# BlinkyTile_Controller.net
KiCad netlist of a schematic drawn in EAGLE
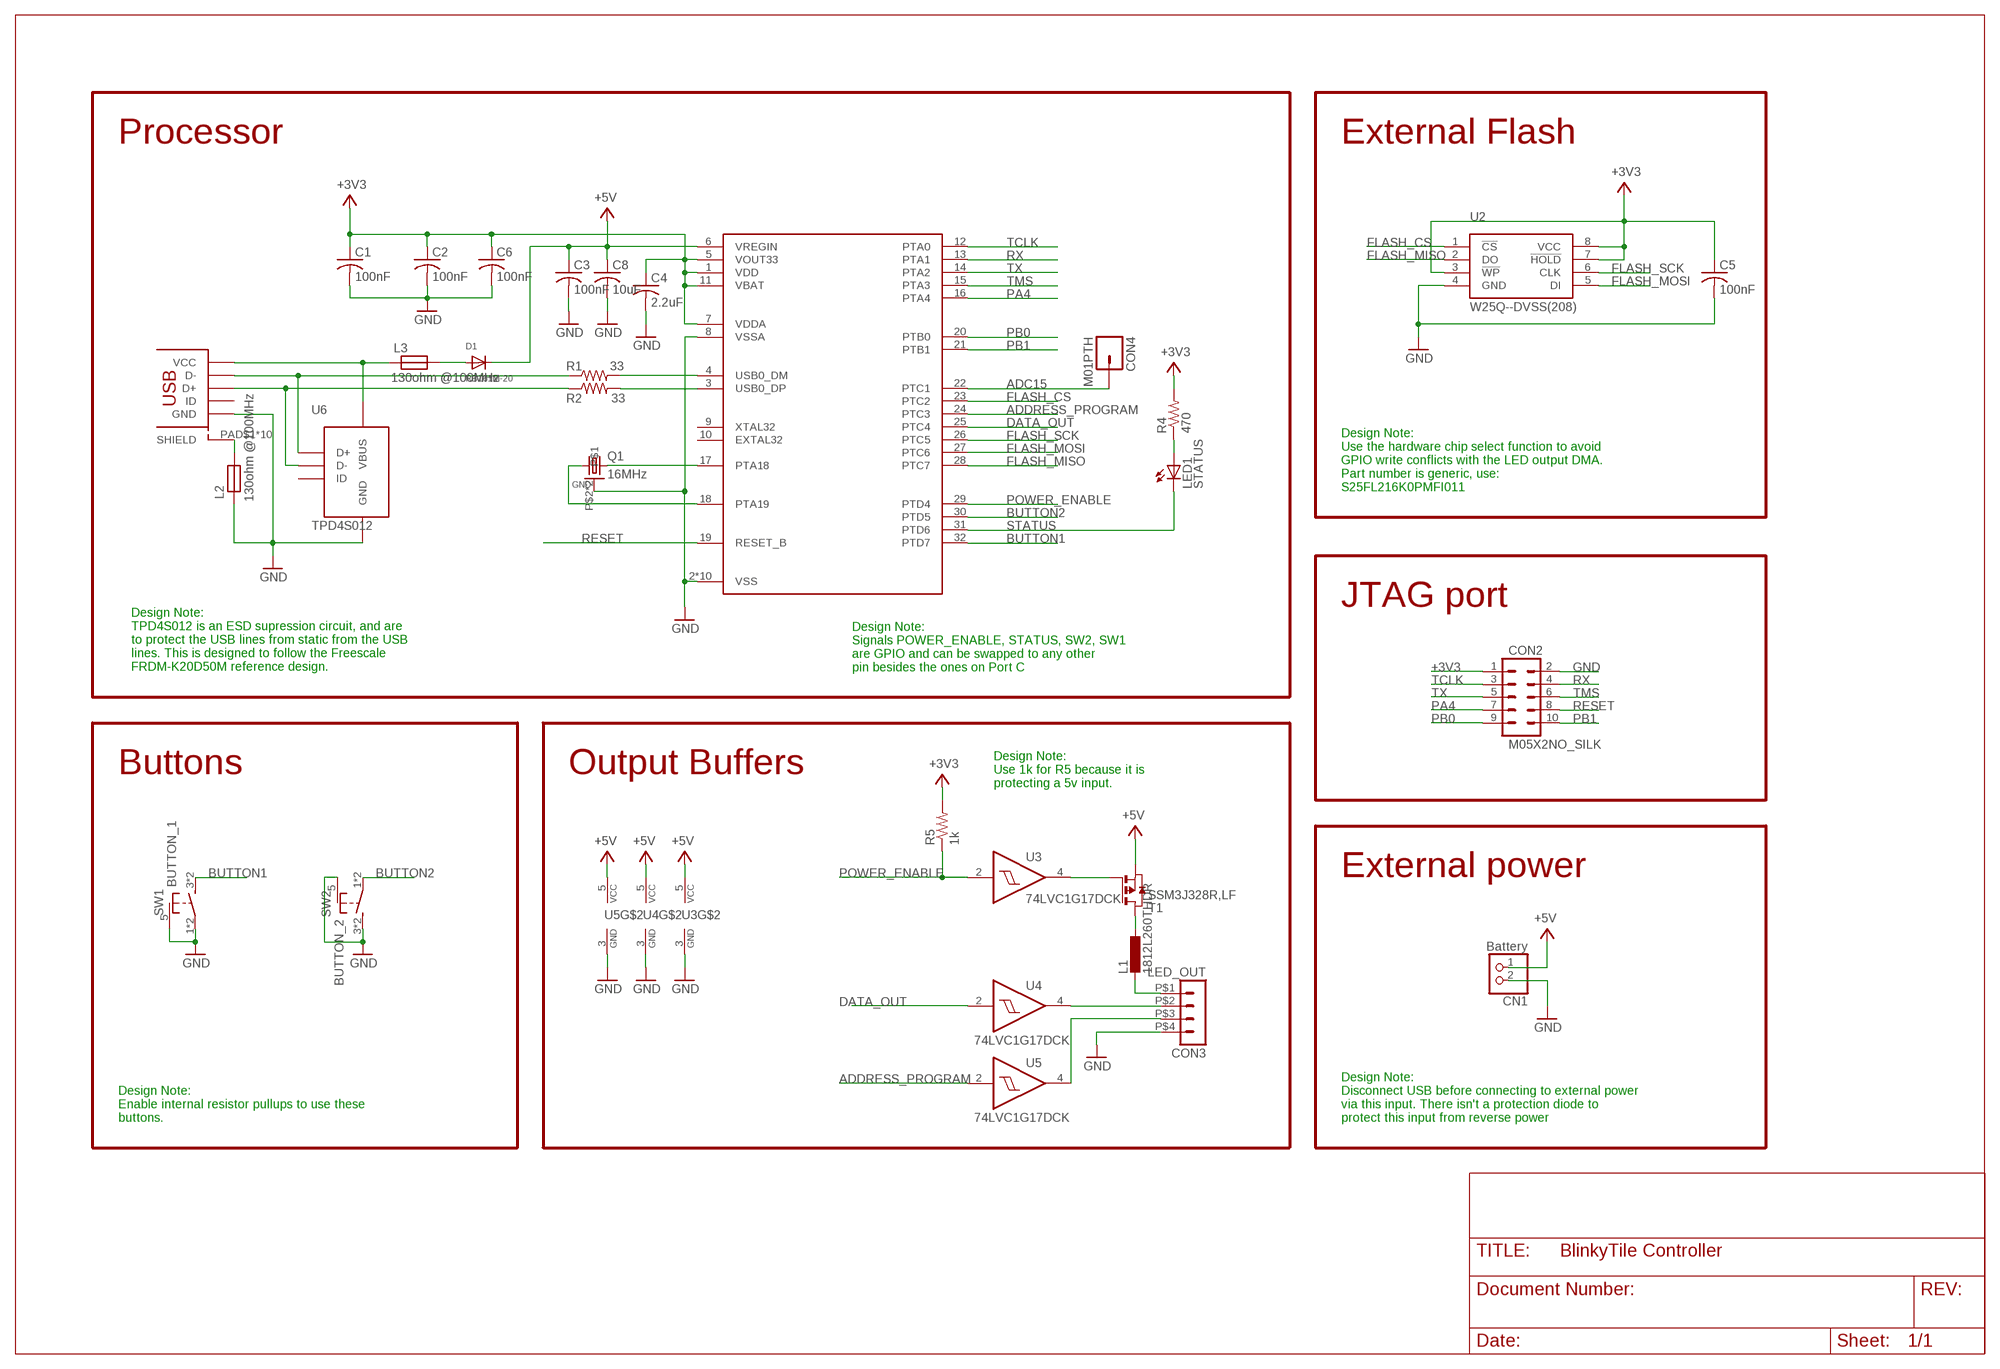
[diagram p0: schematic, sheet 1]

(export (version "E")
  (design (tool "Eeschema 10.0.6"))
  (components
    (comp (ref "C1")
      (value "100nF")
      (footprint "eagle-import:C0402")
      (libsource (lib "eagle-import") (part "C-USC0402"))
    )
    (comp (ref "C2")
      (value "100nF")
      (footprint "eagle-import:C0402")
      (libsource (lib "eagle-import") (part "C-USC0402"))
    )
    (comp (ref "C3")
      (value "100nF")
      (footprint "eagle-import:C0402")
      (libsource (lib "eagle-import") (part "C-USC0402"))
    )
    (comp (ref "C4")
      (value "2.2uF")
      (footprint "eagle-import:C0402")
      (libsource (lib "eagle-import") (part "C-USC0402"))
    )
    (comp (ref "C5")
      (value "100nF")
      (footprint "eagle-import:C0402")
      (libsource (lib "eagle-import") (part "C-USC0402"))
    )
    (comp (ref "C6")
      (value "100nF")
      (footprint "eagle-import:C0402")
      (libsource (lib "eagle-import") (part "C-USC0402"))
    )
    (comp (ref "C8")
      (value "10uF")
      (footprint "eagle-import:C0805K")
      (libsource (lib "eagle-import") (part "C-USC0805K"))
    )
    (comp (ref "CN1")
      (value "Battery")
      (footprint "eagle-import:JST-PH-2-THM-RA")
      (libsource (lib "eagle-import") (part "JST_2PIN-THM-RA"))
    )
    (comp (ref "CON1")
      (value "USB_MICROSMT+THRUHULE")
      (footprint "eagle-import:USB_MICRO_THRUHOLE")
      (libsource (lib "eagle-import") (part "USB_MICROSMT+THRUHULE"))
    )
    (comp (ref "CON2")
      (value "M05X2NO_SILK")
      (footprint "eagle-import:2X5_NOSILK")
      (libsource (lib "eagle-import") (part "M05X2NO_SILK"))
    )
    (comp (ref "CON3")
      (value "LED_OUT")
      (footprint "eagle-import:DUPONT-4P")
      (libsource (lib "eagle-import") (part "4-PIN_DUPONT"))
    )
    (comp (ref "CON4")
      (value "M01PTH")
      (footprint "eagle-import:1X01")
      (libsource (lib "eagle-import") (part "M01PTH"))
    )
    (comp (ref "D1")
      (value "RB161M-20")
      (footprint "eagle-import:SOD-123")
      (libsource (lib "eagle-import") (part "DIODESOD-123"))
    )
    (comp (ref "L1")
      (value "1812L260THDR")
      (footprint "eagle-import:L1812")
      (libsource (lib "eagle-import") (part "L-EUL1812"))
    )
    (comp (ref "L2")
      (value "130ohm @100MHz")
      (footprint "eagle-import:0805")
      (libsource (lib "eagle-import") (part "FB0805/NO-OUTLINE"))
    )
    (comp (ref "L3")
      (value "130ohm @100MHz")
      (footprint "eagle-import:0805")
      (libsource (lib "eagle-import") (part "FB0805/NO-OUTLINE"))
    )
    (comp (ref "LED1")
      (value "STATUS")
      (footprint "eagle-import:CHIPLED_0805")
      (libsource (lib "eagle-import") (part "LEDCHIPLED_0805"))
    )
    (comp (ref "Q1")
      (value "16MHz")
      (footprint "eagle-import:CRSYTAL_2520")
      (libsource (lib "eagle-import") (part "CRYSTAL_4PAD2520"))
    )
    (comp (ref "R1")
      (value "33")
      (footprint "eagle-import:R0402")
      (libsource (lib "eagle-import") (part "R-US_R0402"))
    )
    (comp (ref "R2")
      (value "33")
      (footprint "eagle-import:R0402")
      (libsource (lib "eagle-import") (part "R-US_R0402"))
    )
    (comp (ref "R4")
      (value "470")
      (footprint "eagle-import:R0402")
      (libsource (lib "eagle-import") (part "R-US_R0402"))
    )
    (comp (ref "R5")
      (value "1k")
      (footprint "eagle-import:R0402")
      (libsource (lib "eagle-import") (part "R-US_R0402"))
    )
    (comp (ref "SW1")
      (value "BUTTON_1")
      (footprint "eagle-import:TD-07XB")
      (libsource (lib "eagle-import") (part "BUTTON_MOMENTARY_GROUND"))
    )
    (comp (ref "SW2")
      (value "BUTTON_2")
      (footprint "eagle-import:TD-07XB")
      (libsource (lib "eagle-import") (part "BUTTON_MOMENTARY_GROUND"))
    )
    (comp (ref "T1")
      (value "SSM3J328R,LF")
      (footprint "eagle-import:SOT-23")
      (libsource (lib "eagle-import") (part "PMOSSOT23"))
    )
    (comp (ref "U1")
      (value "MK20D--VFM5")
      (footprint "eagle-import:QFN32_5X5_LONGLEADS")
      (libsource (lib "eagle-import") (part "MK20D--VFM5"))
    )
    (comp (ref "U2")
      (value "W25Q--DVSS(208)")
      (footprint "eagle-import:SOIC8-208")
      (libsource (lib "eagle-import") (part "W25Q--DVSS(208)"))
    )
    (comp (ref "U3")
      (value "74LVC1G17DCK")
      (footprint "eagle-import:SC70-5")
      (libsource (lib "eagle-import") (part "741G17DCKLVC"))
    )
    (comp (ref "U4")
      (value "74LVC1G17DCK")
      (footprint "eagle-import:SC70-5")
      (libsource (lib "eagle-import") (part "741G17DCKLVC"))
    )
    (comp (ref "U5")
      (value "74LVC1G17DCK")
      (footprint "eagle-import:SC70-5")
      (libsource (lib "eagle-import") (part "741G17DCKLVC"))
    )
    (comp (ref "U6")
      (value "TPD4S012")
      (footprint "eagle-import:R-PUSON-N6")
      (libsource (lib "eagle-import") (part "TPD4S012"))
    )
  )
  (nets
    (net (code "1") (name "+3V3") (class "Default")
      (node (ref "C1") (pin "1") (pinfunction "1_1") (pintype "passive"))
      (node (ref "C2") (pin "1") (pinfunction "1_1") (pintype "passive"))
      (node (ref "C4") (pin "1") (pinfunction "1_1") (pintype "passive"))
      (node (ref "C5") (pin "1") (pinfunction "1_1") (pintype "passive"))
      (node (ref "C6") (pin "1") (pinfunction "1_1") (pintype "passive"))
      (node (ref "CON2") (pin "1") (pinfunction "1_1") (pintype "passive"))
      (node (ref "R4") (pin "2") (pinfunction "2_2") (pintype "passive"))
      (node (ref "R5") (pin "2") (pinfunction "2_2") (pintype "passive"))
      (node (ref "U1") (pin "1") (pinfunction "VDD_1") (pintype "bidirectional"))
      (node (ref "U1") (pin "11") (pinfunction "VBAT_11") (pintype "bidirectional"))
      (node (ref "U1") (pin "5") (pinfunction "VOUT33_5") (pintype "bidirectional"))
      (node (ref "U1") (pin "7") (pinfunction "VDDA_7") (pintype "bidirectional"))
      (node (ref "U2") (pin "3") (pinfunction "~{WP}_3") (pintype "bidirectional"))
      (node (ref "U2") (pin "7") (pinfunction "~{HOLD}_7") (pintype "bidirectional"))
      (node (ref "U2") (pin "8") (pinfunction "VCC_8") (pintype "bidirectional"))
    )
    (net (code "2") (name "+5V") (class "Default")
      (node (ref "C3") (pin "1") (pinfunction "1_1") (pintype "passive"))
      (node (ref "C8") (pin "1") (pinfunction "1_1") (pintype "passive"))
      (node (ref "CN1") (pin "1") (pinfunction "2_1") (pintype "passive"))
      (node (ref "D1") (pin "C") (pinfunction "C_C") (pintype "passive"))
      (node (ref "T1") (pin "2") (pinfunction "S_2") (pintype "passive"))
      (node (ref "U1") (pin "6") (pinfunction "VREGIN_6") (pintype "bidirectional"))
      (node (ref "U3") (pin "5") (pinfunction "VCC_5") (pintype "power_in"))
      (node (ref "U4") (pin "5") (pinfunction "VCC_5") (pintype "power_in"))
      (node (ref "U5") (pin "5") (pinfunction "VCC_5") (pintype "power_in"))
    )
    (net (code "3") (name "/ADC15") (class "Default")
      (node (ref "CON4") (pin "1") (pinfunction "1_1") (pintype "passive"))
      (node (ref "U1") (pin "22") (pinfunction "PTC1_22") (pintype "bidirectional"))
    )
    (net (code "4") (name "/ADDRESS_PROGRAM") (class "Default")
      (node (ref "U1") (pin "24") (pinfunction "PTC3_24") (pintype "bidirectional"))
      (node (ref "U5") (pin "2") (pinfunction "I_2") (pintype "input"))
    )
    (net (code "5") (name "/BUTTON1") (class "Default")
      (node (ref "SW1") (pin "3") (pinfunction "S_3") (pintype "passive"))
      (node (ref "SW1") (pin "4") (pinfunction "S_4") (pintype "passive"))
      (node (ref "U1") (pin "32") (pinfunction "PTD7_32") (pintype "bidirectional"))
    )
    (net (code "6") (name "/BUTTON2") (class "Default")
      (node (ref "SW2") (pin "1") (pinfunction "P_1") (pintype "passive"))
      (node (ref "SW2") (pin "2") (pinfunction "P_2") (pintype "passive"))
      (node (ref "U1") (pin "30") (pinfunction "PTD5_30") (pintype "bidirectional"))
    )
    (net (code "7") (name "/DATA_OUT") (class "Default")
      (node (ref "U1") (pin "25") (pinfunction "PTC4_25") (pintype "bidirectional"))
      (node (ref "U4") (pin "2") (pinfunction "I_2") (pintype "input"))
    )
    (net (code "8") (name "/FLASH_CS") (class "Default")
      (node (ref "U1") (pin "23") (pinfunction "PTC2_23") (pintype "bidirectional"))
      (node (ref "U2") (pin "1") (pinfunction "~{CS}_1") (pintype "bidirectional"))
    )
    (net (code "9") (name "/FLASH_MISO") (class "Default")
      (node (ref "U1") (pin "28") (pinfunction "PTC7_28") (pintype "bidirectional"))
      (node (ref "U2") (pin "2") (pinfunction "DO_2") (pintype "bidirectional"))
    )
    (net (code "10") (name "/FLASH_MOSI") (class "Default")
      (node (ref "U1") (pin "27") (pinfunction "PTC6_27") (pintype "bidirectional"))
      (node (ref "U2") (pin "5") (pinfunction "DI_5") (pintype "bidirectional"))
    )
    (net (code "11") (name "/FLASH_SCK") (class "Default")
      (node (ref "U1") (pin "26") (pinfunction "PTC5_26") (pintype "bidirectional"))
      (node (ref "U2") (pin "6") (pinfunction "CLK_6") (pintype "bidirectional"))
    )
    (net (code "12") (name "/PA4") (class "Default")
      (node (ref "CON2") (pin "7") (pinfunction "7_7") (pintype "passive"))
      (node (ref "U1") (pin "16") (pinfunction "PTA4_16") (pintype "bidirectional"))
    )
    (net (code "13") (name "/PB0") (class "Default")
      (node (ref "CON2") (pin "9") (pinfunction "9_9") (pintype "passive"))
      (node (ref "U1") (pin "20") (pinfunction "PTB0_20") (pintype "bidirectional"))
    )
    (net (code "14") (name "/PB1") (class "Default")
      (node (ref "CON2") (pin "10") (pinfunction "10_10") (pintype "passive"))
      (node (ref "U1") (pin "21") (pinfunction "PTB1_21") (pintype "bidirectional"))
    )
    (net (code "15") (name "/POWER_ENABLE") (class "Default")
      (node (ref "R5") (pin "1") (pinfunction "1_1") (pintype "passive"))
      (node (ref "U1") (pin "29") (pinfunction "PTD4_29") (pintype "bidirectional"))
      (node (ref "U3") (pin "2") (pinfunction "I_2") (pintype "input"))
    )
    (net (code "16") (name "/RESET") (class "Default")
      (node (ref "CON2") (pin "8") (pinfunction "8_8") (pintype "passive"))
      (node (ref "U1") (pin "19") (pinfunction "RESET_B_19") (pintype "bidirectional"))
    )
    (net (code "17") (name "/RX") (class "Default")
      (node (ref "CON2") (pin "4") (pinfunction "4_4") (pintype "passive"))
      (node (ref "U1") (pin "13") (pinfunction "PTA1_13") (pintype "bidirectional"))
    )
    (net (code "18") (name "/STATUS") (class "Default")
      (node (ref "LED1") (pin "C") (pinfunction "C_C") (pintype "passive"))
      (node (ref "U1") (pin "31") (pinfunction "PTD6_31") (pintype "bidirectional"))
    )
    (net (code "19") (name "/TCLK") (class "Default")
      (node (ref "CON2") (pin "3") (pinfunction "3_3") (pintype "passive"))
      (node (ref "U1") (pin "12") (pinfunction "PTA0_12") (pintype "bidirectional"))
    )
    (net (code "20") (name "/TMS") (class "Default")
      (node (ref "CON2") (pin "6") (pinfunction "6_6") (pintype "passive"))
      (node (ref "U1") (pin "15") (pinfunction "PTA3_15") (pintype "bidirectional"))
    )
    (net (code "21") (name "/TX") (class "Default")
      (node (ref "CON2") (pin "5") (pinfunction "5_5") (pintype "passive"))
      (node (ref "U1") (pin "14") (pinfunction "PTA2_14") (pintype "bidirectional"))
    )
    (net (code "22") (name "GND") (class "Default")
      (node (ref "C1") (pin "2") (pinfunction "2_2") (pintype "passive"))
      (node (ref "C2") (pin "2") (pinfunction "2_2") (pintype "passive"))
      (node (ref "C3") (pin "2") (pinfunction "2_2") (pintype "passive"))
      (node (ref "C4") (pin "2") (pinfunction "2_2") (pintype "passive"))
      (node (ref "C5") (pin "2") (pinfunction "2_2") (pintype "passive"))
      (node (ref "C6") (pin "2") (pinfunction "2_2") (pintype "passive"))
      (node (ref "C8") (pin "2") (pinfunction "2_2") (pintype "passive"))
      (node (ref "CN1") (pin "2") (pinfunction "1_2") (pintype "passive"))
      (node (ref "CON1") (pin "PIN$5") (pinfunction "GND_PIN$5") (pintype "bidirectional"))
      (node (ref "CON2") (pin "2") (pinfunction "2_2") (pintype "passive"))
      (node (ref "CON3") (pin "P$4") (pinfunction "4_P$4") (pintype "passive"))
      (node (ref "L2") (pin "2") (pinfunction "P$2_2") (pintype "bidirectional"))
      (node (ref "Q1") (pin "P$2") (pinfunction "P$1_P$2") (pintype "bidirectional"))
      (node (ref "Q1") (pin "P$4") (pinfunction "P$1_P$4") (pintype "bidirectional"))
      (node (ref "SW1") (pin "1") (pinfunction "P_1") (pintype "passive"))
      (node (ref "SW1") (pin "2") (pinfunction "P_2") (pintype "passive"))
      (node (ref "SW1") (pin "5") (pinfunction "SHIELD_5") (pintype "passive"))
      (node (ref "SW2") (pin "3") (pinfunction "S_3") (pintype "passive"))
      (node (ref "SW2") (pin "4") (pinfunction "S_4") (pintype "passive"))
      (node (ref "SW2") (pin "5") (pinfunction "SHIELD_5") (pintype "passive"))
      (node (ref "U1") (pin "2") (pinfunction "VSS_2") (pintype "bidirectional"))
      (node (ref "U1") (pin "8") (pinfunction "VSSA_8") (pintype "bidirectional"))
      (node (ref "U1") (pin "PAD@1") (pinfunction "VSS_PAD@1") (pintype "bidirectional"))
      (node (ref "U1") (pin "PAD@10") (pinfunction "VSS_PAD@10") (pintype "bidirectional"))
      (node (ref "U1") (pin "PAD@11") (pinfunction "VSS_PAD@11") (pintype "bidirectional"))
      (node (ref "U1") (pin "PAD@2") (pinfunction "VSS_PAD@2") (pintype "bidirectional"))
      (node (ref "U1") (pin "PAD@3") (pinfunction "VSS_PAD@3") (pintype "bidirectional"))
      (node (ref "U1") (pin "PAD@4") (pinfunction "VSS_PAD@4") (pintype "bidirectional"))
      (node (ref "U1") (pin "PAD@5") (pinfunction "VSS_PAD@5") (pintype "bidirectional"))
      (node (ref "U1") (pin "PAD@6") (pinfunction "VSS_PAD@6") (pintype "bidirectional"))
      (node (ref "U1") (pin "PAD@9") (pinfunction "VSS_PAD@9") (pintype "bidirectional"))
      (node (ref "U2") (pin "4") (pinfunction "GND_4") (pintype "bidirectional"))
      (node (ref "U3") (pin "3") (pinfunction "GND_3") (pintype "power_in"))
      (node (ref "U4") (pin "3") (pinfunction "GND_3") (pintype "power_in"))
      (node (ref "U5") (pin "3") (pinfunction "GND_3") (pintype "power_in"))
      (node (ref "U6") (pin "P$4") (pinfunction "GND_P$4") (pintype "bidirectional"))
    )
    (net (code "23") (name "Net-(CON1-D+)") (class "Default")
      (node (ref "CON1") (pin "PIN$3") (pinfunction "D+_PIN$3") (pintype "bidirectional"))
      (node (ref "R2") (pin "1") (pinfunction "1_1") (pintype "passive"))
      (node (ref "U6") (pin "P$2") (pinfunction "D-_P$2") (pintype "bidirectional"))
    )
    (net (code "24") (name "Net-(CON1-D-)") (class "Default")
      (node (ref "CON1") (pin "PIN$2") (pinfunction "D-_PIN$2") (pintype "bidirectional"))
      (node (ref "R1") (pin "1") (pinfunction "1_1") (pintype "passive"))
      (node (ref "U6") (pin "P$1") (pinfunction "D+_P$1") (pintype "bidirectional"))
    )
    (net (code "25") (name "Net-(CON1-VCC)") (class "Default")
      (node (ref "CON1") (pin "PIN$1") (pinfunction "VCC_PIN$1") (pintype "bidirectional"))
      (node (ref "L3") (pin "2") (pinfunction "P$2_2") (pintype "bidirectional"))
      (node (ref "U6") (pin "P$6") (pinfunction "VBUS_P$6") (pintype "bidirectional"))
    )
    (net (code "26") (name "Net-(CON3-1)") (class "Default")
      (node (ref "CON3") (pin "P$1") (pinfunction "1_P$1") (pintype "passive"))
      (node (ref "L1") (pin "2") (pinfunction "2_2") (pintype "passive"))
    )
    (net (code "27") (name "Net-(CON3-2)") (class "Default")
      (node (ref "CON3") (pin "P$2") (pinfunction "2_P$2") (pintype "passive"))
      (node (ref "U4") (pin "4") (pinfunction "O_4") (pintype "output"))
    )
    (net (code "28") (name "Net-(CON3-3)") (class "Default")
      (node (ref "CON3") (pin "P$3") (pinfunction "3_P$3") (pintype "passive"))
      (node (ref "U5") (pin "4") (pinfunction "O_4") (pintype "output"))
    )
    (net (code "29") (name "Net-(L2-P$1)") (class "Default")
      (node (ref "CON1") (pin "PAD$1") (pinfunction "SHIELD_PAD$1") (pintype "bidirectional"))
      (node (ref "CON1") (pin "PAD$10") (pinfunction "SHIELD_PAD$10") (pintype "bidirectional"))
      (node (ref "CON1") (pin "PAD$2") (pinfunction "SHIELD_PAD$2") (pintype "bidirectional"))
      (node (ref "CON1") (pin "PAD$3") (pinfunction "SHIELD_PAD$3") (pintype "bidirectional"))
      (node (ref "CON1") (pin "PAD$4") (pinfunction "SHIELD_PAD$4") (pintype "bidirectional"))
      (node (ref "CON1") (pin "PAD$5") (pinfunction "SHIELD_PAD$5") (pintype "bidirectional"))
      (node (ref "CON1") (pin "PAD$6") (pinfunction "SHIELD_PAD$6") (pintype "bidirectional"))
      (node (ref "CON1") (pin "PAD$7") (pinfunction "SHIELD_PAD$7") (pintype "bidirectional"))
      (node (ref "CON1") (pin "PAD$8") (pinfunction "SHIELD_PAD$8") (pintype "bidirectional"))
      (node (ref "CON1") (pin "PAD$9") (pinfunction "SHIELD_PAD$9") (pintype "bidirectional"))
      (node (ref "L2") (pin "1") (pinfunction "P$1_1") (pintype "bidirectional"))
    )
    (net (code "30") (name "Net-(L3-P$1)") (class "Default")
      (node (ref "D1") (pin "A") (pinfunction "A_A") (pintype "passive"))
      (node (ref "L3") (pin "1") (pinfunction "P$1_1") (pintype "bidirectional"))
    )
    (net (code "31") (name "Net-(LED1-PadA)") (class "Default")
      (node (ref "LED1") (pin "A") (pinfunction "A_A") (pintype "passive"))
      (node (ref "R4") (pin "1") (pinfunction "1_1") (pintype "passive"))
    )
    (net (code "32") (name "Net-(Q1-1)") (class "Default")
      (node (ref "Q1") (pin "P$1") (pinfunction "1_P$1") (pintype "passive"))
      (node (ref "U1") (pin "18") (pinfunction "PTA19_18") (pintype "bidirectional"))
    )
    (net (code "33") (name "Net-(Q1-2)") (class "Default")
      (node (ref "Q1") (pin "P$3") (pinfunction "2_P$3") (pintype "passive"))
      (node (ref "U1") (pin "17") (pinfunction "PTA18_17") (pintype "bidirectional"))
    )
    (net (code "34") (name "Net-(T1-D)") (class "Default")
      (node (ref "L1") (pin "1") (pinfunction "1_1") (pintype "passive"))
      (node (ref "T1") (pin "1") (pinfunction "D_1") (pintype "passive"))
    )
    (net (code "35") (name "Net-(T1-G)") (class "Default")
      (node (ref "T1") (pin "3") (pinfunction "G_3") (pintype "passive"))
      (node (ref "U3") (pin "4") (pinfunction "O_4") (pintype "output"))
    )
    (net (code "36") (name "Net-(U1-USB0_DM)") (class "Default")
      (node (ref "R1") (pin "2") (pinfunction "2_2") (pintype "passive"))
      (node (ref "U1") (pin "4") (pinfunction "USB0_DM_4") (pintype "bidirectional"))
    )
    (net (code "37") (name "Net-(U1-USB0_DP)") (class "Default")
      (node (ref "R2") (pin "2") (pinfunction "2_2") (pintype "passive"))
      (node (ref "U1") (pin "3") (pinfunction "USB0_DP_3") (pintype "bidirectional"))
    )
    (net (code "38") (name "unconnected-(CON1-ID-PadPIN$4)") (class "Default")
      (node (ref "CON1") (pin "PIN$4") (pinfunction "ID_PIN$4") (pintype "bidirectional"))
    )
    (net (code "39") (name "unconnected-(U1-EXTAL32-Pad10)") (class "Default")
      (node (ref "U1") (pin "10") (pinfunction "EXTAL32_10") (pintype "bidirectional"))
    )
    (net (code "40") (name "unconnected-(U1-XTAL32-Pad9)") (class "Default")
      (node (ref "U1") (pin "9") (pinfunction "XTAL32_9") (pintype "bidirectional"))
    )
    (net (code "41") (name "unconnected-(U6-ID-PadP$3)") (class "Default")
      (node (ref "U6") (pin "P$3") (pinfunction "ID_P$3") (pintype "bidirectional"))
    )
  )
)
